# LightSwitch.net
KiCad netlist of a schematic drawn in EAGLE
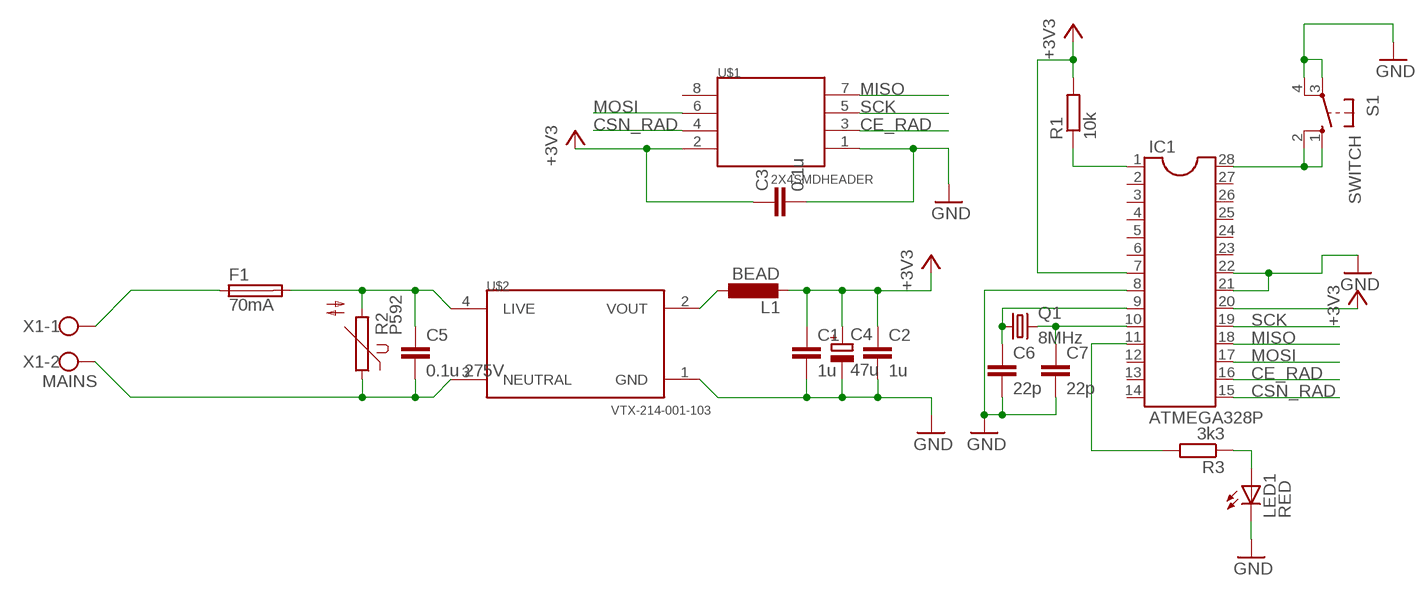
[diagram p0: schematic, sheet 1]

(export (version "E")
  (design (tool "Eeschema 10.0.6"))
  (components
    (comp (ref "C1")
      (value "1u")
      (footprint "eagle-import:C025-025X050")
      (libsource (lib "eagle-import") (part "C-EU025-025X050"))
    )
    (comp (ref "C2")
      (value "1u")
      (footprint "eagle-import:C1206")
      (libsource (lib "eagle-import") (part "C-EUC1206"))
    )
    (comp (ref "C3")
      (value "0.1u")
      (footprint "eagle-import:C1206")
      (libsource (lib "eagle-import") (part "C-EUC1206"))
    )
    (comp (ref "C4")
      (value "47u")
      (footprint "eagle-import:E2,5-6E")
      (libsource (lib "eagle-import") (part "CPOL-EUE2,5-6E"))
    )
    (comp (ref "C5")
      (value "0.1u 275V")
      (footprint "eagle-import:C15B5")
      (libsource (lib "eagle-import") (part "C15/5"))
    )
    (comp (ref "C6")
      (value "22p")
      (footprint "eagle-import:C1206")
      (libsource (lib "eagle-import") (part "C-EUC1206"))
    )
    (comp (ref "C7")
      (value "22p")
      (footprint "eagle-import:C1206")
      (libsource (lib "eagle-import") (part "C-EUC1206"))
    )
    (comp (ref "F1")
      (value "70mA")
      (footprint "eagle-import:SH25")
      (fields (field (name "MF") "SCHURTER") (field (name "MPN") "0031.8211"))
      (libsource (lib "eagle-import") (part "SH25"))
    )
    (comp (ref "IC1")
      (value "ATMEGA328P")
      (footprint "eagle-import:DIL28-3")
      (libsource (lib "eagle-import") (part "DIL28-3"))
    )
    (comp (ref "L1")
      (value "BEAD")
      (footprint "eagle-import:L3230M")
      (libsource (lib "eagle-import") (part "L-EUL3230M"))
    )
    (comp (ref "LED1")
      (value "RED")
      (footprint "eagle-import:LED5MM")
      (libsource (lib "eagle-import") (part "LED5MM"))
    )
    (comp (ref "Q1")
      (value "8MHz")
      (footprint "eagle-import:HC49U70")
      (libsource (lib "eagle-import") (part "CRYSTALHC49U70"))
    )
    (comp (ref "R1")
      (value "10k")
      (footprint "eagle-import:R1206")
      (libsource (lib "eagle-import") (part "R-EU_R1206"))
    )
    (comp (ref "R2")
      (value "P592")
      (footprint "eagle-import:P592")
      (libsource (lib "eagle-import") (part "P592"))
    )
    (comp (ref "R3")
      (value "3k3")
      (footprint "eagle-import:R1206")
      (libsource (lib "eagle-import") (part "R-EU_R1206"))
    )
    (comp (ref "S1")
      (value "SWITCH")
      (footprint "eagle-import:B3F-40XX")
      (fields (field (name "MF") "OMRON COMPONENTS USA") (field (name "MPN") "B3F-4000"))
      (libsource (lib "eagle-import") (part "40-XX"))
    )
    (comp (ref "U$1")
      (value "2X4SMDHEADER")
      (footprint "eagle-import:TSM-110-XX-XXX-DV")
      (libsource (lib "eagle-import") (part "2X4SMDHEADER"))
    )
    (comp (ref "U$2")
      (value "VTX-214-001-103")
      (footprint "eagle-import:VTX214001103")
      (libsource (lib "eagle-import") (part "VTX-214-001-103"))
    )
    (comp (ref "X1")
      (value "MAINS")
      (footprint "eagle-import:W237-102")
      (fields (field (name "MPN") "237-102"))
      (libsource (lib "eagle-import") (part "W237-102"))
    )
  )
  (nets
    (net (code "1") (name "+3V3") (class "Default")
      (node (ref "C1") (pin "1") (pinfunction "1_1") (pintype "passive"))
      (node (ref "C2") (pin "1") (pinfunction "1_1") (pintype "passive"))
      (node (ref "C3") (pin "1") (pinfunction "1_1") (pintype "passive"))
      (node (ref "C4") (pin "+") (pinfunction "+_+") (pintype "passive"))
      (node (ref "IC1") (pin "20") (pinfunction "20_20") (pintype "passive"))
      (node (ref "IC1") (pin "7") (pinfunction "7_7") (pintype "passive"))
      (node (ref "L1") (pin "2") (pinfunction "2_2") (pintype "passive"))
      (node (ref "R1") (pin "2") (pinfunction "2_2") (pintype "passive"))
      (node (ref "U$1") (pin "2") (pinfunction "2_2") (pintype "bidirectional"))
    )
    (net (code "2") (name "/CE_RAD") (class "Default")
      (node (ref "IC1") (pin "16") (pinfunction "16_16") (pintype "passive"))
      (node (ref "U$1") (pin "3") (pinfunction "3_3") (pintype "bidirectional"))
    )
    (net (code "3") (name "/CSN_RAD") (class "Default")
      (node (ref "IC1") (pin "15") (pinfunction "15_15") (pintype "passive"))
      (node (ref "U$1") (pin "4") (pinfunction "4_4") (pintype "bidirectional"))
    )
    (net (code "4") (name "/MISO") (class "Default")
      (node (ref "IC1") (pin "18") (pinfunction "18_18") (pintype "passive"))
      (node (ref "U$1") (pin "7") (pinfunction "7_7") (pintype "bidirectional"))
    )
    (net (code "5") (name "/MOSI") (class "Default")
      (node (ref "IC1") (pin "17") (pinfunction "17_17") (pintype "passive"))
      (node (ref "U$1") (pin "6") (pinfunction "6_6") (pintype "bidirectional"))
    )
    (net (code "6") (name "/SCK") (class "Default")
      (node (ref "IC1") (pin "19") (pinfunction "19_19") (pintype "passive"))
      (node (ref "U$1") (pin "5") (pinfunction "5_5") (pintype "bidirectional"))
    )
    (net (code "7") (name "GND") (class "Default")
      (node (ref "C1") (pin "2") (pinfunction "2_2") (pintype "passive"))
      (node (ref "C2") (pin "2") (pinfunction "2_2") (pintype "passive"))
      (node (ref "C3") (pin "2") (pinfunction "2_2") (pintype "passive"))
      (node (ref "C4") (pin "-") (pinfunction "-_-") (pintype "passive"))
      (node (ref "C6") (pin "2") (pinfunction "2_2") (pintype "passive"))
      (node (ref "C7") (pin "2") (pinfunction "2_2") (pintype "passive"))
      (node (ref "IC1") (pin "21") (pinfunction "21_21") (pintype "passive"))
      (node (ref "IC1") (pin "22") (pinfunction "22_22") (pintype "passive"))
      (node (ref "IC1") (pin "8") (pinfunction "8_8") (pintype "passive"))
      (node (ref "LED1") (pin "K") (pinfunction "C_K") (pintype "passive"))
      (node (ref "S1") (pin "3") (pinfunction "P_3") (pintype "passive"))
      (node (ref "S1") (pin "4") (pinfunction "P1_4") (pintype "passive"))
      (node (ref "U$1") (pin "1") (pinfunction "1_1") (pintype "bidirectional"))
      (node (ref "U$2") (pin "1") (pinfunction "GND_1") (pintype "power_in"))
    )
    (net (code "8") (name "Net-(C6-Pad1)") (class "Default")
      (node (ref "C6") (pin "1") (pinfunction "1_1") (pintype "passive"))
      (node (ref "IC1") (pin "9") (pinfunction "9_9") (pintype "passive"))
      (node (ref "Q1") (pin "1") (pinfunction "1_1") (pintype "passive"))
    )
    (net (code "9") (name "Net-(C7-Pad1)") (class "Default")
      (node (ref "C7") (pin "1") (pinfunction "1_1") (pintype "passive"))
      (node (ref "IC1") (pin "10") (pinfunction "10_10") (pintype "passive"))
      (node (ref "Q1") (pin "2") (pinfunction "2_2") (pintype "passive"))
    )
    (net (code "10") (name "Net-(IC1-Pad1)") (class "Default")
      (node (ref "IC1") (pin "1") (pinfunction "1_1") (pintype "passive"))
      (node (ref "R1") (pin "1") (pinfunction "1_1") (pintype "passive"))
    )
    (net (code "11") (name "Net-(IC1-Pad11)") (class "Default")
      (node (ref "IC1") (pin "11") (pinfunction "11_11") (pintype "passive"))
      (node (ref "R3") (pin "2") (pinfunction "2_2") (pintype "passive"))
    )
    (net (code "12") (name "Net-(LED1-PadA)") (class "Default")
      (node (ref "LED1") (pin "A") (pinfunction "A_A") (pintype "passive"))
      (node (ref "R3") (pin "1") (pinfunction "1_1") (pintype "passive"))
    )
    (net (code "13") (name "Net-(S1-S)") (class "Default")
      (node (ref "IC1") (pin "28") (pinfunction "28_28") (pintype "passive"))
      (node (ref "S1") (pin "1") (pinfunction "S_1") (pintype "passive"))
      (node (ref "S1") (pin "2") (pinfunction "S1_2") (pintype "passive"))
    )
    (net (code "14") (name "Net-(U$2-LIVE)") (class "Default")
      (node (ref "C5") (pin "1") (pinfunction "1_1") (pintype "passive"))
      (node (ref "F1") (pin "2") (pinfunction "2_2") (pintype "passive"))
      (node (ref "R2") (pin "2") (pinfunction "2_2") (pintype "passive"))
      (node (ref "U$2") (pin "4") (pinfunction "LIVE_4") (pintype "input"))
    )
    (net (code "15") (name "Net-(U$2-NEUTRAL)") (class "Default")
      (node (ref "C5") (pin "2") (pinfunction "2_2") (pintype "passive"))
      (node (ref "R2") (pin "1") (pinfunction "1_1") (pintype "passive"))
      (node (ref "U$2") (pin "3") (pinfunction "NEUTRAL_3") (pintype "input"))
      (node (ref "X1") (pin "2") (pinfunction "KL_2") (pintype "passive"))
    )
    (net (code "16") (name "Net-(U$2-VOUT)") (class "Default")
      (node (ref "L1") (pin "1") (pinfunction "1_1") (pintype "passive"))
      (node (ref "U$2") (pin "2") (pinfunction "VOUT_2") (pintype "power_in"))
    )
    (net (code "17") (name "Net-(X1A-KL)") (class "Default")
      (node (ref "F1") (pin "1") (pinfunction "1_1") (pintype "passive"))
      (node (ref "X1") (pin "1") (pinfunction "KL_1") (pintype "passive"))
    )
    (net (code "18") (name "unconnected-(IC1-Pad2)") (class "Default")
      (node (ref "IC1") (pin "2") (pinfunction "2_2") (pintype "passive"))
    )
    (net (code "19") (name "unconnected-(IC1-Pad3)") (class "Default")
      (node (ref "IC1") (pin "3") (pinfunction "3_3") (pintype "passive"))
    )
    (net (code "20") (name "unconnected-(IC1-Pad4)") (class "Default")
      (node (ref "IC1") (pin "4") (pinfunction "4_4") (pintype "passive"))
    )
    (net (code "21") (name "unconnected-(IC1-Pad5)") (class "Default")
      (node (ref "IC1") (pin "5") (pinfunction "5_5") (pintype "passive"))
    )
    (net (code "22") (name "unconnected-(IC1-Pad6)") (class "Default")
      (node (ref "IC1") (pin "6") (pinfunction "6_6") (pintype "passive"))
    )
    (net (code "23") (name "unconnected-(IC1-Pad12)") (class "Default")
      (node (ref "IC1") (pin "12") (pinfunction "12_12") (pintype "passive"))
    )
    (net (code "24") (name "unconnected-(IC1-Pad13)") (class "Default")
      (node (ref "IC1") (pin "13") (pinfunction "13_13") (pintype "passive"))
    )
    (net (code "25") (name "unconnected-(IC1-Pad14)") (class "Default")
      (node (ref "IC1") (pin "14") (pinfunction "14_14") (pintype "passive"))
    )
    (net (code "26") (name "unconnected-(IC1-Pad23)") (class "Default")
      (node (ref "IC1") (pin "23") (pinfunction "23_23") (pintype "passive"))
    )
    (net (code "27") (name "unconnected-(IC1-Pad24)") (class "Default")
      (node (ref "IC1") (pin "24") (pinfunction "24_24") (pintype "passive"))
    )
    (net (code "28") (name "unconnected-(IC1-Pad25)") (class "Default")
      (node (ref "IC1") (pin "25") (pinfunction "25_25") (pintype "passive"))
    )
    (net (code "29") (name "unconnected-(IC1-Pad26)") (class "Default")
      (node (ref "IC1") (pin "26") (pinfunction "26_26") (pintype "passive"))
    )
    (net (code "30") (name "unconnected-(IC1-Pad27)") (class "Default")
      (node (ref "IC1") (pin "27") (pinfunction "27_27") (pintype "passive"))
    )
    (net (code "31") (name "unconnected-(U$1-Pad8)") (class "Default")
      (node (ref "U$1") (pin "8") (pinfunction "8_8") (pintype "bidirectional"))
    )
  )
)
